# Hackcard.net
KiCad netlist of a schematic drawn in EasyEDA Pro
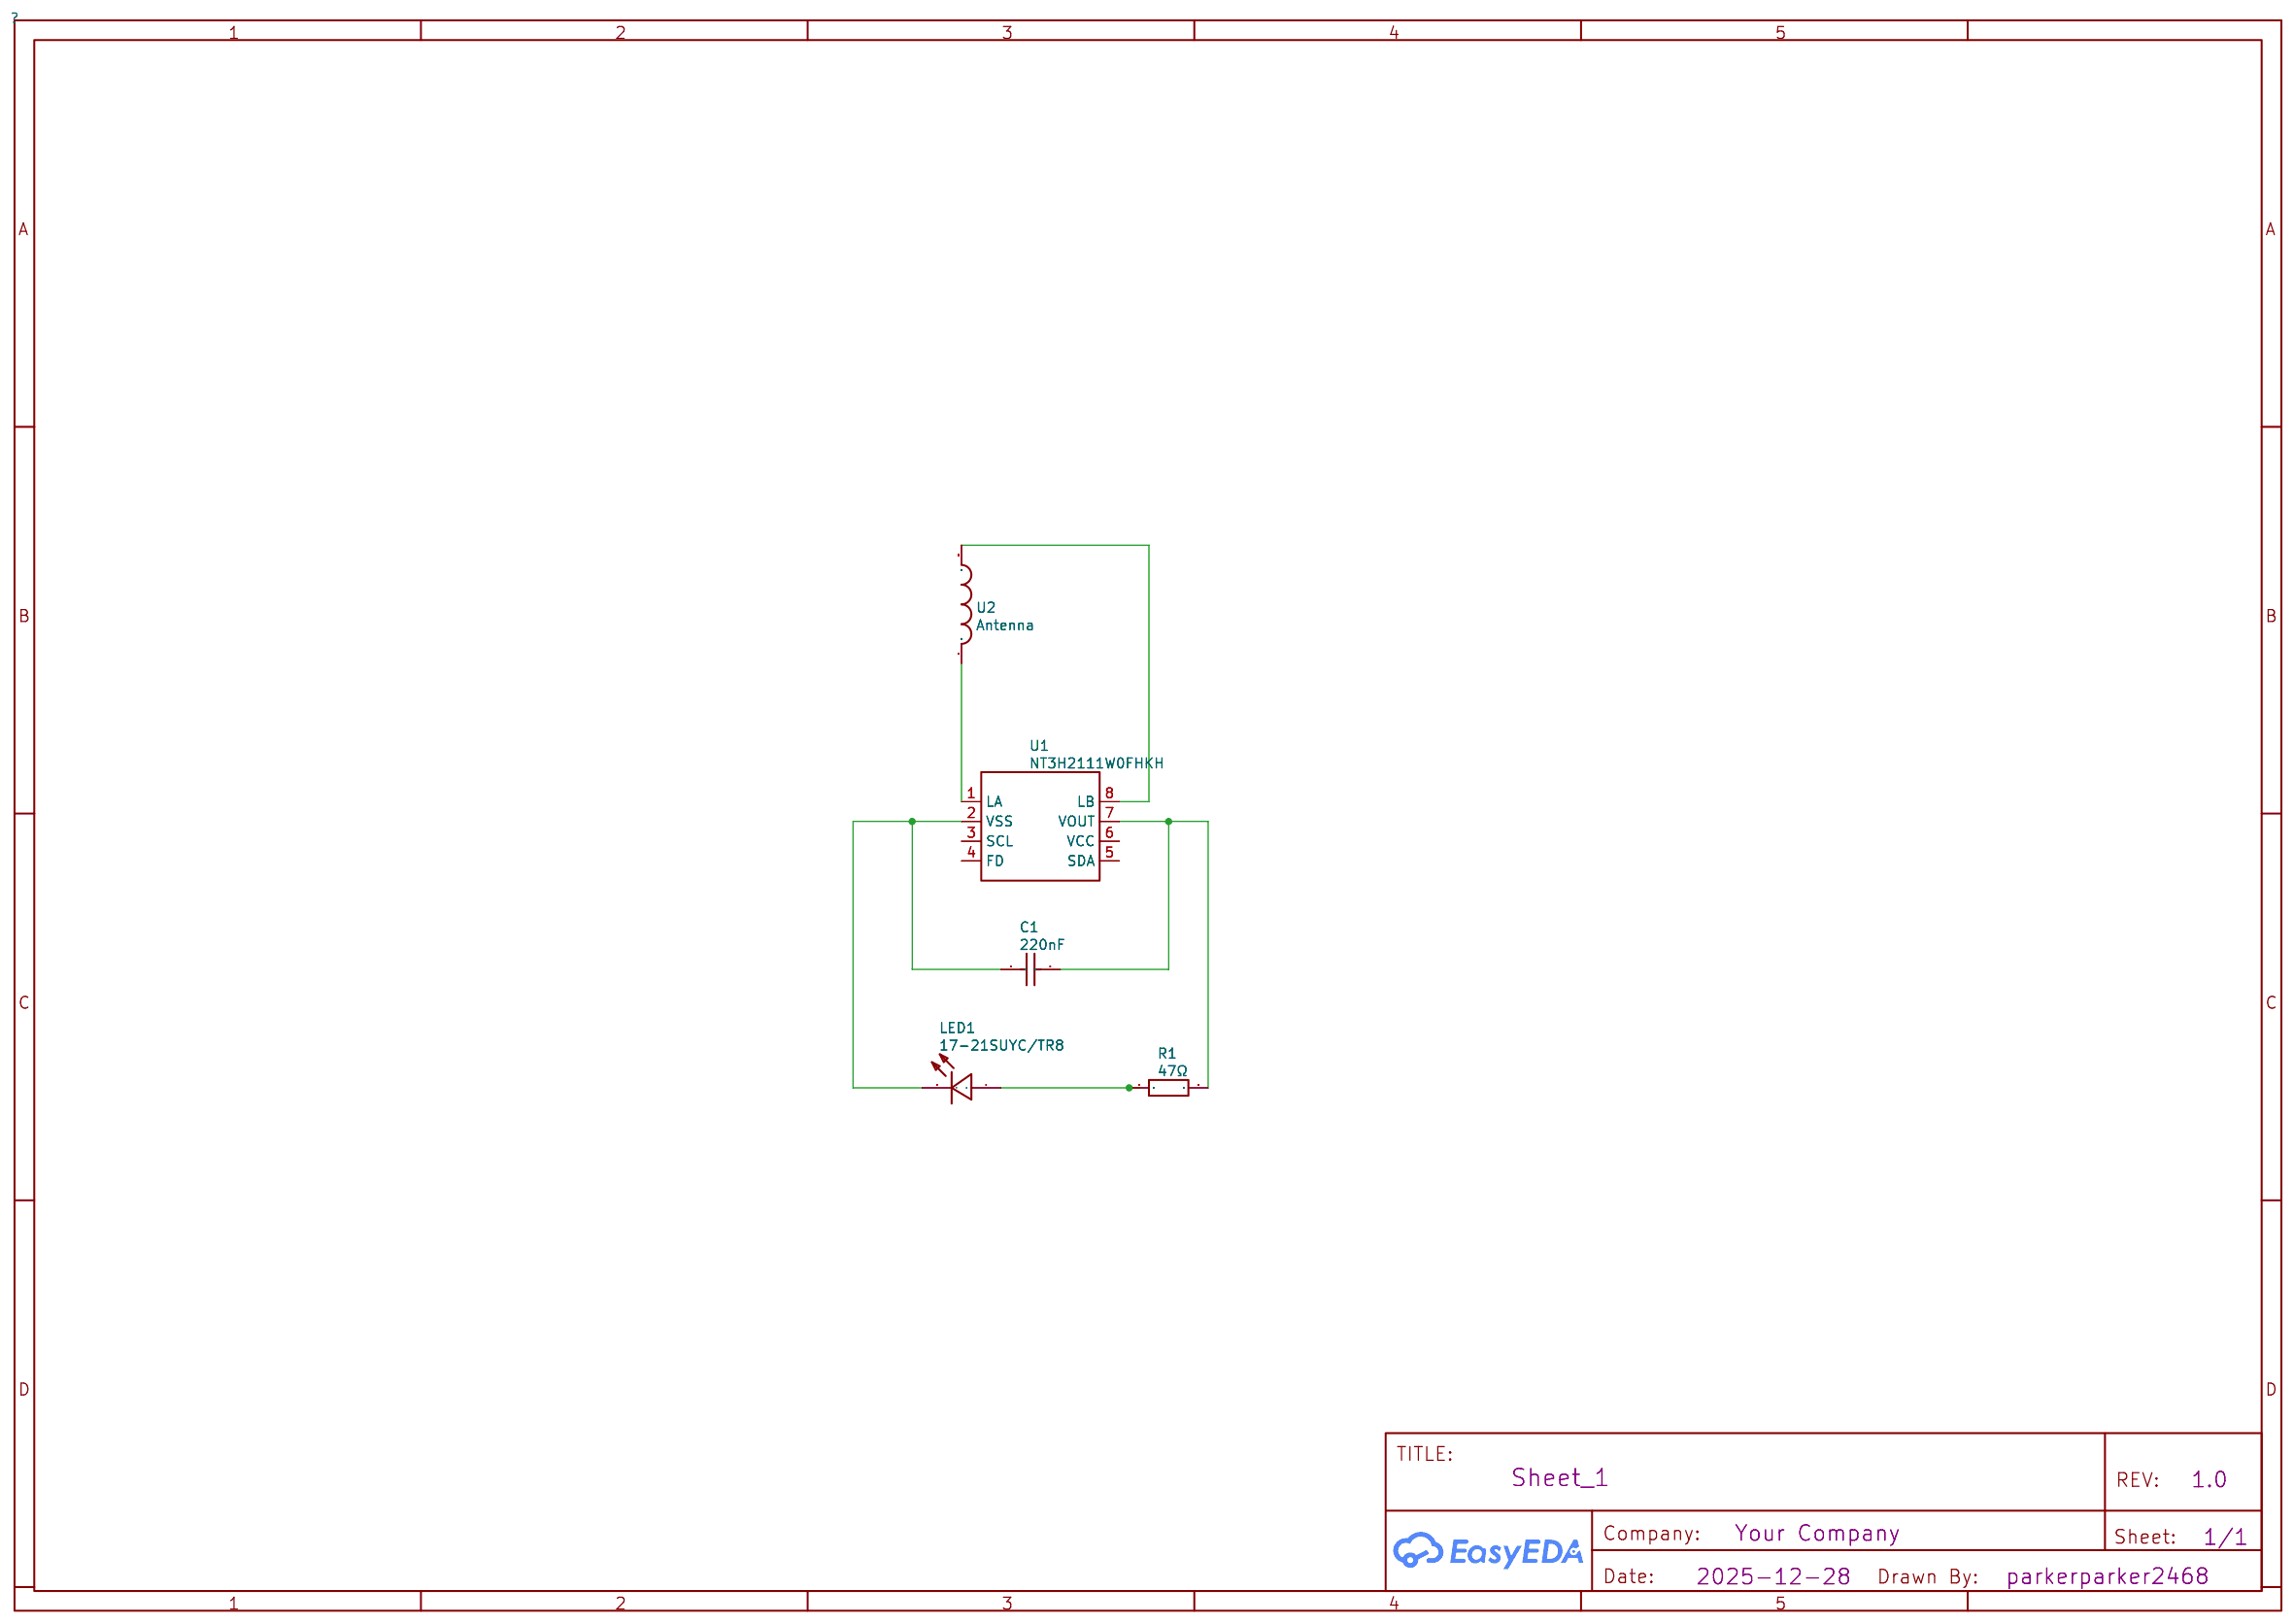
[diagram p0: schematic sheet]

(export (version "E")
  (design (tool "Eeschema 10.0.6"))
  (components
    (comp (ref "C1")
      (value "220nF")
      (footprint "easyedapro:C0603")
      (fields
        (field (name "Manufacturer Part") "CL10B224KA8NNNC")
        (field (name "Manufacturer") "SAMSUNG(三星)")
      )
      (libsource (lib "easyedapro") (part "220nF"))
    )
    (comp (ref "LED1")
      (value "17-21SUYC/TR8")
      (footprint "easyedapro:LED0805-R-RD")
      (fields (field (name "Manufacturer Part") "KT-0805黄灯") (field (name "Manufacturer") "KENTO"))
      (libsource (lib "easyedapro") (part "17-21SUYC/TR8"))
    )
    (comp (ref "R1")
      (value "47Ω")
      (footprint "easyedapro:R0603")
      (fields
        (field (name "Manufacturer Part") "0603WAF470JT5E")
        (field (name "Manufacturer") "UNI-ROYAL(厚声)")
      )
      (libsource (lib "easyedapro") (part "47Ω"))
    )
    (comp (ref "U1")
      (value "NT3H2111W0FHKH")
      (footprint "easyedapro:XQFN-8_L1.6-W1.6-P0.50-BL_NT3H2111W0FHKH")
      (fields (field (name "Manufacturer") "NXP(恩智浦)") (field (name "Contributor") "LCSC"))
      (libsource (lib "easyedapro") (part "NT3H2111W0FHKH"))
    )
    (comp (ref "U2")
      (value "Antenna")
      (footprint "easyedapro:25X48MM_NFC_ANTENNA")
      (fields (field (name "Contributor") "maggie.j.liu"))
      (libsource (lib "easyedapro") (part "Antenna"))
    )
  )
  (nets
    (net (code "1") (name "Net-(LED1-+)") (class "Default")
      (node (ref "LED1") (pin "1") (pinfunction "+_1") (pintype "unspecified"))
      (node (ref "R1") (pin "1") (pinfunction "1_1") (pintype "input"))
    )
    (net (code "2") (name "Net-(LED1--)") (class "Default")
      (node (ref "C1") (pin "1") (pinfunction "1_1") (pintype "input"))
      (node (ref "LED1") (pin "2") (pinfunction "-_2") (pintype "unspecified"))
      (node (ref "U1") (pin "2") (pinfunction "VSS_2") (pintype "unspecified"))
    )
    (net (code "3") (name "Net-(U1-LA)") (class "Default")
      (node (ref "U1") (pin "1") (pinfunction "LA_1") (pintype "unspecified"))
      (node (ref "U2") (pin "P$1") (pinfunction "P$1_P$1") (pintype "unspecified"))
    )
    (net (code "4") (name "Net-(U1-LB)") (class "Default")
      (node (ref "U1") (pin "8") (pinfunction "LB_8") (pintype "unspecified"))
      (node (ref "U2") (pin "P$2") (pinfunction "P$2_P$2") (pintype "unspecified"))
    )
    (net (code "5") (name "Net-(U1-VOUT)") (class "Default")
      (node (ref "C1") (pin "2") (pinfunction "2_2") (pintype "input"))
      (node (ref "R1") (pin "2") (pinfunction "2_2") (pintype "input"))
      (node (ref "U1") (pin "7") (pinfunction "VOUT_7") (pintype "unspecified"))
    )
    (net (code "6") (name "unconnected-(U1-FD-Pad4)") (class "Default")
      (node (ref "U1") (pin "4") (pinfunction "FD_4") (pintype "unspecified"))
    )
    (net (code "7") (name "unconnected-(U1-SCL-Pad3)") (class "Default")
      (node (ref "U1") (pin "3") (pinfunction "SCL_3") (pintype "unspecified"))
    )
    (net (code "8") (name "unconnected-(U1-SDA-Pad5)") (class "Default")
      (node (ref "U1") (pin "5") (pinfunction "SDA_5") (pintype "unspecified"))
    )
    (net (code "9") (name "unconnected-(U1-VCC-Pad6)") (class "Default")
      (node (ref "U1") (pin "6") (pinfunction "VCC_6") (pintype "unspecified"))
    )
  )
)
